# Controller.net
KiCad netlist of a schematic drawn in Altium Designer
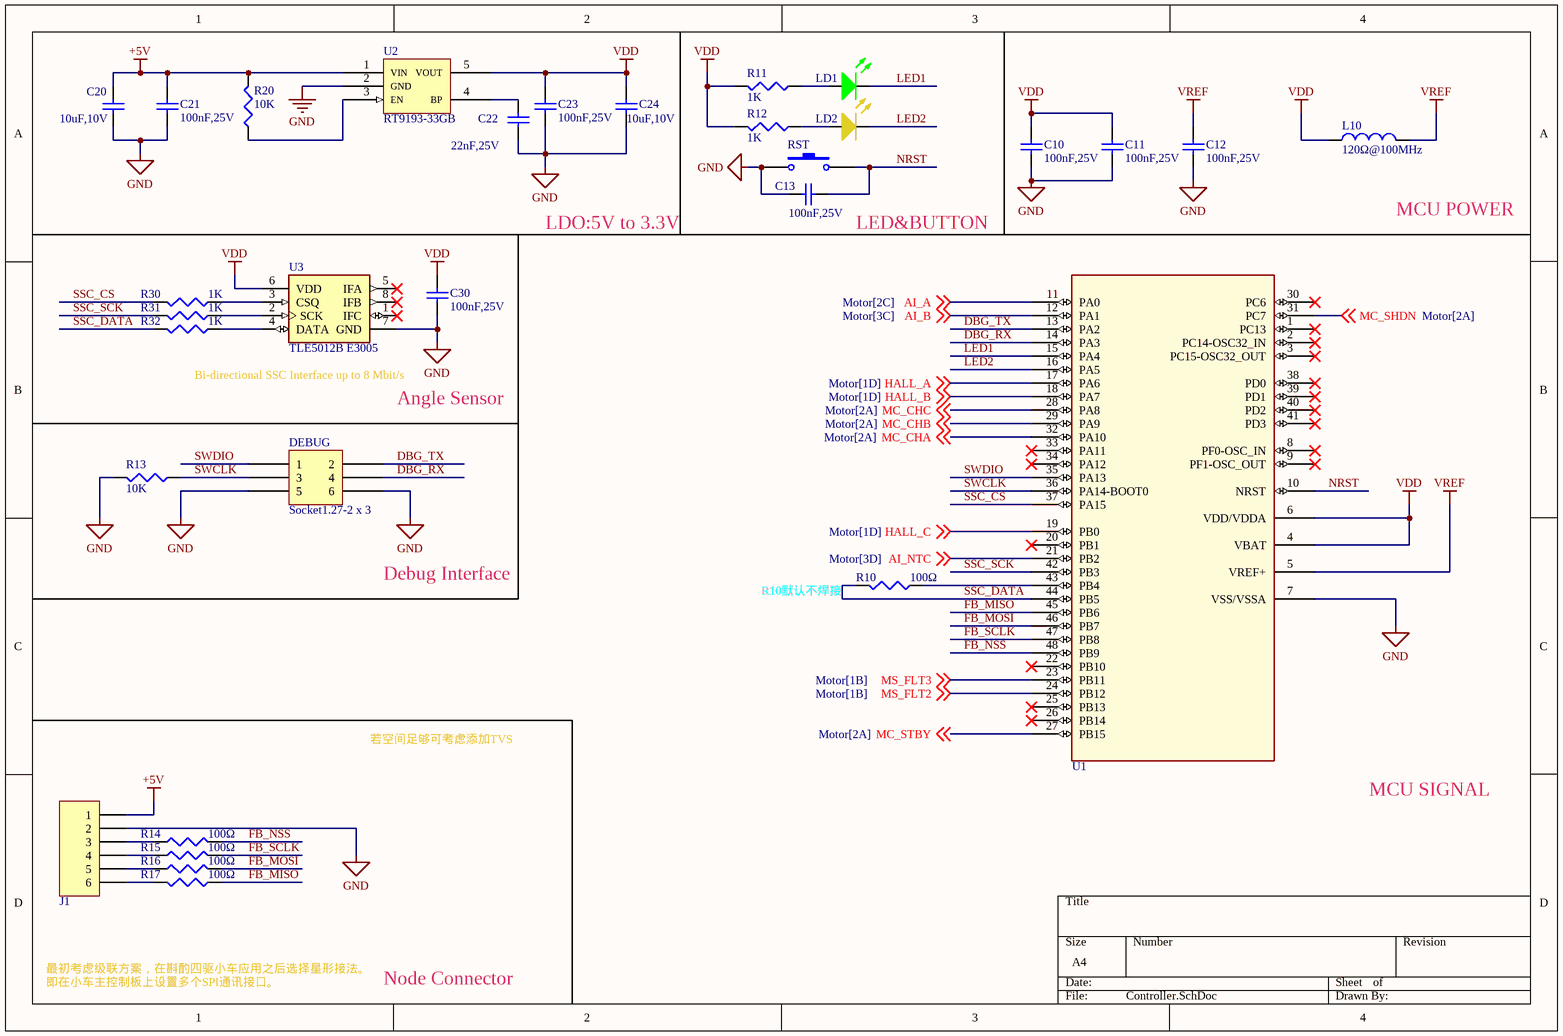
[diagram p0: Controller.SchDoc]

(export (version "E")
  (design (tool "Eeschema 10.0.6"))
  (components
    (comp (ref "C10")
      (value "100nF,25V")
      (footprint "CAPC1005L")
      (description "MLCC, 0402(1005)")
      (fields (field (name "Comment") "MLCC") (field (name "PUBLISHER") "Altium Limited"))
      (libsource (lib "Miscellaneous Devices") (part "Cap"))
    )
    (comp (ref "C11")
      (value "100nF,25V")
      (footprint "CAPC1005L")
      (description "MLCC, 0402(1005)")
      (fields (field (name "Comment") "MLCC") (field (name "PUBLISHER") "Altium Limited"))
      (libsource (lib "Miscellaneous Devices") (part "Cap"))
    )
    (comp (ref "C12")
      (value "100nF,25V")
      (footprint "CAPC1005L")
      (description "MLCC, 0402(1005)")
      (fields (field (name "Comment") "MLCC") (field (name "PUBLISHER") "Altium Limited"))
      (libsource (lib "Miscellaneous Devices") (part "Cap"))
    )
    (comp (ref "C13")
      (value "100nF,25V")
      (footprint "CAPC1005L")
      (description "MLCC, 0402(1005)")
      (fields (field (name "Comment") "MLCC") (field (name "PUBLISHER") "Altium Limited"))
      (libsource (lib "Miscellaneous Devices") (part "Cap"))
    )
    (comp (ref "C20")
      (value "10uF,10V")
      (footprint "CAPC1608L")
      (description "MLCC, 0603(1608)")
      (fields (field (name "Comment") "MLCC") (field (name "PUBLISHER") "Altium Limited"))
      (libsource (lib "Miscellaneous Devices") (part "Cap"))
    )
    (comp (ref "C21")
      (value "100nF,25V")
      (footprint "CAPC1005L")
      (description "MLCC, 0402(1005)")
      (fields (field (name "Comment") "MLCC") (field (name "PUBLISHER") "Altium Limited"))
      (libsource (lib "Miscellaneous Devices") (part "Cap"))
    )
    (comp (ref "C22")
      (value "22nF,25V")
      (footprint "CAPC1005L")
      (description "MLCC, 0402(1005)")
      (fields (field (name "Comment") "MLCC") (field (name "PUBLISHER") "Altium Limited"))
      (libsource (lib "Miscellaneous Devices") (part "Cap"))
    )
    (comp (ref "C23")
      (value "100nF,25V")
      (footprint "CAPC1005L")
      (description "MLCC, 0402(1005)")
      (fields (field (name "Comment") "MLCC") (field (name "PUBLISHER") "Altium Limited"))
      (libsource (lib "Miscellaneous Devices") (part "Cap"))
    )
    (comp (ref "C24")
      (value "10uF,10V")
      (footprint "CAPC1608L")
      (description "MLCC, 0603(1608)")
      (fields (field (name "Comment") "MLCC") (field (name "PUBLISHER") "Altium Limited"))
      (libsource (lib "Miscellaneous Devices") (part "Cap"))
    )
    (comp (ref "C30")
      (value "100nF,25V")
      (footprint "CAPC1005L")
      (description "MLCC, 0402(1005)")
      (fields (field (name "Comment") "MLCC") (field (name "PUBLISHER") "Altium Limited"))
      (libsource (lib "Miscellaneous Devices") (part "Cap"))
    )
    (comp (ref "DEBUG")
      (value "Socket1.27-2 x 3")
      (footprint "Socket_1.27_V_2 x 03")
      (description "Socket with 1.27mm gap, 3x2 pins")
      (libsource (lib "XSS_Connector") (part "Socket1.27-3x2"))
    )
    (comp (ref "J1")
      (value "B6B-PH-K-S")
      (footprint "B6B-PH-K-S")
      (description "B6B-PH-K-S or PH2.0 vertical throughhole,5 pins,Gap:2mm")
      (libsource (lib "XSS_Connector") (part "B6B-PH-K-S"))
    )
    (comp (ref "L10")
      (value "120Ω@100MHz")
      (footprint "0402-A")
      (description "Ferrite Bead")
      (fields (field (name "Comment") "Inductor") (field (name "PUBLISHER") "Altium Limited"))
      (libsource (lib "Miscellaneous Devices") (part "Inductor"))
    )
    (comp (ref "LD1")
      (value "LED_0603_GREEN")
      (footprint "LED_0603_AK_Green")
      (description "GREEN LED, 0603")
      (libsource (lib "XSS_IC") (part "LED_0603_GREEN"))
    )
    (comp (ref "LD2")
      (value "LED")
      (footprint "LED_0603_AK_Yellow")
      (description "YELLOW LED, 0603")
      (libsource (lib "XSS_IC") (part "LED_0603_YELLOW"))
    )
    (comp (ref "R10")
      (value "100Ω")
      (footprint "RESC1005L")
      (description "Resistor, 0402(1005)")
      (fields (field (name "Comment") "RES, SMT") (field (name "PUBLISHER") "Altium Limited"))
      (libsource (lib "Miscellaneous Devices") (part "Res3"))
    )
    (comp (ref "R11")
      (value "1K")
      (footprint "RESC1005L")
      (description "Resistor, 0402(1005)")
      (fields (field (name "Comment") "RES, SMT") (field (name "PUBLISHER") "Altium Limited"))
      (libsource (lib "Miscellaneous Devices") (part "Res3"))
    )
    (comp (ref "R12")
      (value "1K")
      (footprint "RESC1005L")
      (description "Resistor, 0402(1005)")
      (fields (field (name "Comment") "RES, SMT") (field (name "PUBLISHER") "Altium Limited"))
      (libsource (lib "Miscellaneous Devices") (part "Res3"))
    )
    (comp (ref "R13")
      (value "10K")
      (footprint "RESC1005L")
      (description "Resistor, 0402(1005)")
      (fields (field (name "Comment") "RES, SMT") (field (name "PUBLISHER") "Altium Limited"))
      (libsource (lib "Miscellaneous Devices") (part "Res3"))
    )
    (comp (ref "R14")
      (value "100Ω")
      (footprint "RESC1005L")
      (description "Resistor, 0402(1005)")
      (fields (field (name "Comment") "RES, SMT") (field (name "PUBLISHER") "Altium Limited"))
      (libsource (lib "Miscellaneous Devices") (part "Res3"))
    )
    (comp (ref "R15")
      (value "100Ω")
      (footprint "RESC1005L")
      (description "Resistor, 0402(1005)")
      (fields (field (name "Comment") "RES, SMT") (field (name "PUBLISHER") "Altium Limited"))
      (libsource (lib "Miscellaneous Devices") (part "Res3"))
    )
    (comp (ref "R16")
      (value "100Ω")
      (footprint "RESC1005L")
      (description "Resistor, 0402(1005)")
      (fields (field (name "Comment") "RES, SMT") (field (name "PUBLISHER") "Altium Limited"))
      (libsource (lib "Miscellaneous Devices") (part "Res3"))
    )
    (comp (ref "R17")
      (value "100Ω")
      (footprint "RESC1005L")
      (description "Resistor, 0402(1005)")
      (fields (field (name "Comment") "RES, SMT") (field (name "PUBLISHER") "Altium Limited"))
      (libsource (lib "Miscellaneous Devices") (part "Res3"))
    )
    (comp (ref "R20")
      (value "10K")
      (footprint "RESC1005L")
      (description "Resistor, 0402(1005)")
      (fields (field (name "Comment") "RES, SMT") (field (name "PUBLISHER") "Altium Limited"))
      (libsource (lib "Miscellaneous Devices") (part "Res3"))
    )
    (comp (ref "R30")
      (value "1K")
      (footprint "RESC1005L")
      (description "Resistor, 0402(1005)")
      (fields (field (name "Comment") "RES, SMT") (field (name "PUBLISHER") "Altium Limited"))
      (libsource (lib "Miscellaneous Devices") (part "Res3"))
    )
    (comp (ref "R31")
      (value "1K")
      (footprint "RESC1005L")
      (description "Resistor, 0402(1005)")
      (fields (field (name "Comment") "RES, SMT") (field (name "PUBLISHER") "Altium Limited"))
      (libsource (lib "Miscellaneous Devices") (part "Res3"))
    )
    (comp (ref "R32")
      (value "1K")
      (footprint "RESC1005L")
      (description "Resistor, 0402(1005)")
      (fields (field (name "Comment") "RES, SMT") (field (name "PUBLISHER") "Altium Limited"))
      (libsource (lib "Miscellaneous Devices") (part "Res3"))
    )
    (comp (ref "RST")
      (value "switch")
      (footprint "SW2_3*2*0.6")
      (libsource (lib "XSS_IC") (part "SW-SPST-2P"))
    )
    (comp (ref "U1")
      (value "STM32G070CBT6")
      (footprint "LQFP48-L")
      (fields
        (field (name "MANUFACTURER_PART_NUMBER") "stm32g0_lqfp48_t2")
        (field (name "COPYRIGHT") "Copyright (C) 2018 Accelerated Designs. All rights reserved")
      )
      (libsource (lib "ST Microelectronics STM32 G0") (part "STM32G070CBTx"))
    )
    (comp (ref "U2")
      (value "RT9193-33GB")
      (footprint "SOT-25")
      (description "RICHTEK RT9193-xxGB with SOT-23-5. xx could be 15...50(1.5V...5.0V),1H(1.85V),2H(2.85V),4G(4.75V).")
      (libsource (lib "XSS_IC") (part "RT9193-xxGB"))
    )
    (comp (ref "U3")
      (value "TLE5012B E3005")
      (footprint "Infineon_PG-DSO-8")
      (description "Infineon, TLE5012B magnetic angle sensor for steering angle measurement. SOIC-8(PG-DSO-8) package.")
      (libsource (lib "XSS_IC") (part "TLE5012B"))
    )
  )
  (nets
    (net (code "1") (name "+5V") (class "Default")
      (node (ref "C20") (pin "2") (pinfunction "2_2") (pintype "passive"))
      (node (ref "C21") (pin "2") (pinfunction "2_2") (pintype "passive"))
      (node (ref "J1") (pin "1") (pinfunction "1_1") (pintype "passive"))
      (node (ref "R20") (pin "2") (pinfunction "2_2") (pintype "passive"))
      (node (ref "U2") (pin "1") (pinfunction "VIN_1") (pintype "power_in"))
    )
    (net (code "2") (name "/DBG_RX") (class "Default")
      (node (ref "DEBUG") (pin "4") (pinfunction "4_4") (pintype "passive"))
      (node (ref "U1") (pin "14") (pinfunction "PA3_14") (pintype "bidirectional"))
    )
    (net (code "3") (name "/DBG_TX") (class "Default")
      (node (ref "DEBUG") (pin "2") (pinfunction "2_2") (pintype "passive"))
      (node (ref "U1") (pin "13") (pinfunction "PA2_13") (pintype "bidirectional"))
    )
    (net (code "4") (name "/FB_MISO") (class "Default")
      (node (ref "R17") (pin "1") (pinfunction "1_1") (pintype "passive"))
      (node (ref "U1") (pin "45") (pinfunction "PB6_45") (pintype "bidirectional"))
    )
    (net (code "5") (name "/FB_MOSI") (class "Default")
      (node (ref "R16") (pin "2") (pinfunction "2_2") (pintype "passive"))
      (node (ref "U1") (pin "46") (pinfunction "PB7_46") (pintype "bidirectional"))
    )
    (net (code "6") (name "/FB_NSS") (class "Default")
      (node (ref "R14") (pin "2") (pinfunction "2_2") (pintype "passive"))
      (node (ref "U1") (pin "48") (pinfunction "PB9_48") (pintype "bidirectional"))
    )
    (net (code "7") (name "/FB_SCLK") (class "Default")
      (node (ref "R15") (pin "2") (pinfunction "2_2") (pintype "passive"))
      (node (ref "U1") (pin "47") (pinfunction "PB8_47") (pintype "bidirectional"))
    )
    (net (code "8") (name "/LED1") (class "Default")
      (node (ref "LD1") (pin "K") (pinfunction "K_K") (pintype "passive"))
      (node (ref "U1") (pin "15") (pinfunction "PA4_15") (pintype "bidirectional"))
    )
    (net (code "9") (name "/LED2") (class "Default")
      (node (ref "LD2") (pin "K") (pinfunction "K_K") (pintype "passive"))
      (node (ref "U1") (pin "16") (pinfunction "PA5_16") (pintype "bidirectional"))
    )
    (net (code "10") (name "/NRST") (class "Default")
      (node (ref "C13") (pin "1") (pinfunction "1_1") (pintype "passive"))
      (node (ref "RST") (pin "2") (pinfunction "2_2") (pintype "passive"))
      (node (ref "U1") (pin "10") (pinfunction "NRST_10") (pintype "bidirectional"))
    )
    (net (code "11") (name "/SSC_CS") (class "Default")
      (node (ref "R30") (pin "2") (pinfunction "2_2") (pintype "passive"))
      (node (ref "U1") (pin "37") (pinfunction "PA15_37") (pintype "bidirectional"))
    )
    (net (code "12") (name "/SSC_DATA") (class "Default")
      (node (ref "R10") (pin "2") (pinfunction "2_2") (pintype "passive"))
      (node (ref "R32") (pin "2") (pinfunction "2_2") (pintype "passive"))
      (node (ref "U1") (pin "44") (pinfunction "PB5_44") (pintype "bidirectional"))
    )
    (net (code "13") (name "/SSC_SCK") (class "Default")
      (node (ref "R31") (pin "2") (pinfunction "2_2") (pintype "passive"))
      (node (ref "U1") (pin "42") (pinfunction "PB3_42") (pintype "bidirectional"))
    )
    (net (code "14") (name "/SWCLK") (class "Default")
      (node (ref "DEBUG") (pin "3") (pinfunction "3_3") (pintype "passive"))
      (node (ref "R13") (pin "1") (pinfunction "1_1") (pintype "passive"))
      (node (ref "U1") (pin "36") (pinfunction "PA14-BOOT0_36") (pintype "bidirectional"))
    )
    (net (code "15") (name "/SWDIO") (class "Default")
      (node (ref "DEBUG") (pin "1") (pinfunction "1_1") (pintype "passive"))
      (node (ref "U1") (pin "35") (pinfunction "PA13_35") (pintype "bidirectional"))
    )
    (net (code "16") (name "AI_A") (class "Default")
      (node (ref "U1") (pin "11") (pinfunction "PA0_11") (pintype "bidirectional"))
    )
    (net (code "17") (name "AI_B") (class "Default")
      (node (ref "U1") (pin "12") (pinfunction "PA1_12") (pintype "bidirectional"))
    )
    (net (code "18") (name "AI_NTC") (class "Default")
      (node (ref "U1") (pin "21") (pinfunction "PB2_21") (pintype "bidirectional"))
    )
    (net (code "19") (name "GND") (class "Default")
      (node (ref "C10") (pin "1") (pinfunction "1_1") (pintype "passive"))
      (node (ref "C11") (pin "1") (pinfunction "1_1") (pintype "passive"))
      (node (ref "C12") (pin "1") (pinfunction "1_1") (pintype "passive"))
      (node (ref "C13") (pin "2") (pinfunction "2_2") (pintype "passive"))
      (node (ref "C20") (pin "1") (pinfunction "1_1") (pintype "passive"))
      (node (ref "C21") (pin "1") (pinfunction "1_1") (pintype "passive"))
      (node (ref "C22") (pin "1") (pinfunction "1_1") (pintype "passive"))
      (node (ref "C23") (pin "1") (pinfunction "1_1") (pintype "passive"))
      (node (ref "C24") (pin "1") (pinfunction "1_1") (pintype "passive"))
      (node (ref "C30") (pin "1") (pinfunction "1_1") (pintype "passive"))
      (node (ref "DEBUG") (pin "5") (pinfunction "5_5") (pintype "passive"))
      (node (ref "DEBUG") (pin "6") (pinfunction "6_6") (pintype "passive"))
      (node (ref "J1") (pin "2") (pinfunction "2_2") (pintype "passive"))
      (node (ref "R13") (pin "2") (pinfunction "2_2") (pintype "passive"))
      (node (ref "RST") (pin "1") (pinfunction "1_1") (pintype "passive"))
      (node (ref "U1") (pin "7") (pinfunction "VSS/VSSA_7") (pintype "power_in"))
      (node (ref "U2") (pin "2") (pinfunction "GND_2") (pintype "power_in"))
      (node (ref "U3") (pin "7") (pinfunction "GND_7") (pintype "power_in"))
    )
    (net (code "20") (name "HALL_A") (class "Default")
      (node (ref "U1") (pin "17") (pinfunction "PA6_17") (pintype "bidirectional"))
    )
    (net (code "21") (name "HALL_B") (class "Default")
      (node (ref "U1") (pin "18") (pinfunction "PA7_18") (pintype "bidirectional"))
    )
    (net (code "22") (name "HALL_C") (class "Default")
      (node (ref "U1") (pin "19") (pinfunction "PB0_19") (pintype "bidirectional"))
    )
    (net (code "23") (name "MC_CHA") (class "Default")
      (node (ref "U1") (pin "32") (pinfunction "PA10_32") (pintype "bidirectional"))
    )
    (net (code "24") (name "MC_CHB") (class "Default")
      (node (ref "U1") (pin "29") (pinfunction "PA9_29") (pintype "bidirectional"))
    )
    (net (code "25") (name "MC_CHC") (class "Default")
      (node (ref "U1") (pin "28") (pinfunction "PA8_28") (pintype "bidirectional"))
    )
    (net (code "26") (name "MC_SHDN") (class "Default")
      (node (ref "U1") (pin "31") (pinfunction "PC7_31") (pintype "bidirectional"))
    )
    (net (code "27") (name "MC_STBY") (class "Default")
      (node (ref "U1") (pin "27") (pinfunction "PB15_27") (pintype "bidirectional"))
    )
    (net (code "28") (name "MS_FLT2") (class "Default")
      (node (ref "U1") (pin "24") (pinfunction "PB12_24") (pintype "bidirectional"))
    )
    (net (code "29") (name "MS_FLT3") (class "Default")
      (node (ref "U1") (pin "23") (pinfunction "PB11_23") (pintype "bidirectional"))
    )
    (net (code "30") (name "Net-(J1-Pad3)") (class "Default")
      (node (ref "J1") (pin "3") (pinfunction "3_3") (pintype "passive"))
      (node (ref "R14") (pin "1") (pinfunction "1_1") (pintype "passive"))
    )
    (net (code "31") (name "Net-(J1-Pad4)") (class "Default")
      (node (ref "J1") (pin "4") (pinfunction "4_4") (pintype "passive"))
      (node (ref "R15") (pin "1") (pinfunction "1_1") (pintype "passive"))
    )
    (net (code "32") (name "Net-(J1-Pad5)") (class "Default")
      (node (ref "J1") (pin "5") (pinfunction "5_5") (pintype "passive"))
      (node (ref "R16") (pin "1") (pinfunction "1_1") (pintype "passive"))
    )
    (net (code "33") (name "Net-(J1-Pad6)") (class "Default")
      (node (ref "J1") (pin "6") (pinfunction "6_6") (pintype "passive"))
      (node (ref "R17") (pin "2") (pinfunction "2_2") (pintype "passive"))
    )
    (net (code "34") (name "Net-(LD1-PadA)") (class "Default")
      (node (ref "LD1") (pin "A") (pinfunction "A_A") (pintype "passive"))
      (node (ref "R11") (pin "1") (pinfunction "1_1") (pintype "passive"))
    )
    (net (code "35") (name "Net-(LD2-PadA)") (class "Default")
      (node (ref "LD2") (pin "A") (pinfunction "A_A") (pintype "passive"))
      (node (ref "R12") (pin "1") (pinfunction "1_1") (pintype "passive"))
    )
    (net (code "36") (name "Net-(U1-PB4)") (class "Default")
      (node (ref "R10") (pin "1") (pinfunction "1_1") (pintype "passive"))
      (node (ref "U1") (pin "43") (pinfunction "PB4_43") (pintype "bidirectional"))
    )
    (net (code "37") (name "Net-(U2-BP)") (class "Default")
      (node (ref "C22") (pin "2") (pinfunction "2_2") (pintype "passive"))
      (node (ref "U2") (pin "4") (pinfunction "BP_4") (pintype "passive"))
    )
    (net (code "38") (name "Net-(U2-EN)") (class "Default")
      (node (ref "R20") (pin "1") (pinfunction "1_1") (pintype "passive"))
      (node (ref "U2") (pin "3") (pinfunction "EN_3") (pintype "input"))
    )
    (net (code "39") (name "Net-(U3-CSQ)") (class "Default")
      (node (ref "R30") (pin "1") (pinfunction "1_1") (pintype "passive"))
      (node (ref "U3") (pin "3") (pinfunction "CSQ_3") (pintype "input"))
    )
    (net (code "40") (name "Net-(U3-DATA)") (class "Default")
      (node (ref "R32") (pin "1") (pinfunction "1_1") (pintype "passive"))
      (node (ref "U3") (pin "4") (pinfunction "DATA_4") (pintype "bidirectional"))
    )
    (net (code "41") (name "Net-(U3-SCK)") (class "Default")
      (node (ref "R31") (pin "1") (pinfunction "1_1") (pintype "passive"))
      (node (ref "U3") (pin "2") (pinfunction "SCK_2") (pintype "input"))
    )
    (net (code "42") (name "VDD") (class "Default")
      (node (ref "C10") (pin "2") (pinfunction "2_2") (pintype "passive"))
      (node (ref "C11") (pin "2") (pinfunction "2_2") (pintype "passive"))
      (node (ref "C23") (pin "2") (pinfunction "2_2") (pintype "passive"))
      (node (ref "C24") (pin "2") (pinfunction "2_2") (pintype "passive"))
      (node (ref "C30") (pin "2") (pinfunction "2_2") (pintype "passive"))
      (node (ref "L10") (pin "2") (pinfunction "2_2") (pintype "passive"))
      (node (ref "R11") (pin "2") (pinfunction "2_2") (pintype "passive"))
      (node (ref "R12") (pin "2") (pinfunction "2_2") (pintype "passive"))
      (node (ref "U1") (pin "4") (pinfunction "VBAT_4") (pintype "power_in"))
      (node (ref "U1") (pin "6") (pinfunction "VDD/VDDA_6") (pintype "power_in"))
      (node (ref "U2") (pin "5") (pinfunction "VOUT_5") (pintype "power_in"))
      (node (ref "U3") (pin "6") (pinfunction "VDD_6") (pintype "power_in"))
    )
    (net (code "43") (name "VREF") (class "Default")
      (node (ref "C12") (pin "2") (pinfunction "2_2") (pintype "passive"))
      (node (ref "L10") (pin "1") (pinfunction "1_1") (pintype "passive"))
      (node (ref "U1") (pin "5") (pinfunction "VREF+_5") (pintype "power_in"))
    )
    (net (code "44") (name "unconnected-(U1-PA11-Pad33)") (class "Default")
      (node (ref "U1") (pin "33") (pinfunction "PA11_33") (pintype "bidirectional+no_connect"))
    )
    (net (code "45") (name "unconnected-(U1-PA12-Pad34)") (class "Default")
      (node (ref "U1") (pin "34") (pinfunction "PA12_34") (pintype "bidirectional+no_connect"))
    )
    (net (code "46") (name "unconnected-(U1-PB1-Pad20)") (class "Default")
      (node (ref "U1") (pin "20") (pinfunction "PB1_20") (pintype "bidirectional+no_connect"))
    )
    (net (code "47") (name "unconnected-(U1-PB10-Pad22)") (class "Default")
      (node (ref "U1") (pin "22") (pinfunction "PB10_22") (pintype "bidirectional+no_connect"))
    )
    (net (code "48") (name "unconnected-(U1-PB13-Pad25)") (class "Default")
      (node (ref "U1") (pin "25") (pinfunction "PB13_25") (pintype "bidirectional+no_connect"))
    )
    (net (code "49") (name "unconnected-(U1-PB14-Pad26)") (class "Default")
      (node (ref "U1") (pin "26") (pinfunction "PB14_26") (pintype "bidirectional+no_connect"))
    )
    (net (code "50") (name "unconnected-(U1-PC6-Pad30)") (class "Default")
      (node (ref "U1") (pin "30") (pinfunction "PC6_30") (pintype "bidirectional+no_connect"))
    )
    (net (code "51") (name "unconnected-(U1-PC13-Pad1)") (class "Default")
      (node (ref "U1") (pin "1") (pinfunction "PC13_1") (pintype "bidirectional+no_connect"))
    )
    (net (code "52") (name "unconnected-(U1-PC14-OSC32_IN-Pad2)") (class "Default")
      (node (ref "U1") (pin "2") (pinfunction "PC14-OSC32_IN_2") (pintype "bidirectional+no_connect"))
    )
    (net (code "53") (name "unconnected-(U1-PC15-OSC32_OUT-Pad3)") (class "Default")
      (node (ref "U1") (pin "3") (pinfunction "PC15-OSC32_OUT_3") (pintype "bidirectional+no_connect"))
    )
    (net (code "54") (name "unconnected-(U1-PD0-Pad38)") (class "Default")
      (node (ref "U1") (pin "38") (pinfunction "PD0_38") (pintype "bidirectional+no_connect"))
    )
    (net (code "55") (name "unconnected-(U1-PD1-Pad39)") (class "Default")
      (node (ref "U1") (pin "39") (pinfunction "PD1_39") (pintype "bidirectional+no_connect"))
    )
    (net (code "56") (name "unconnected-(U1-PD2-Pad40)") (class "Default")
      (node (ref "U1") (pin "40") (pinfunction "PD2_40") (pintype "bidirectional+no_connect"))
    )
    (net (code "57") (name "unconnected-(U1-PD3-Pad41)") (class "Default")
      (node (ref "U1") (pin "41") (pinfunction "PD3_41") (pintype "bidirectional+no_connect"))
    )
    (net (code "58") (name "unconnected-(U1-PF0-OSC_IN-Pad8)") (class "Default")
      (node (ref "U1") (pin "8") (pinfunction "PF0-OSC_IN_8") (pintype "bidirectional+no_connect"))
    )
    (net (code "59") (name "unconnected-(U1-PF1-OSC_OUT-Pad9)") (class "Default")
      (node (ref "U1") (pin "9") (pinfunction "PF1-OSC_OUT_9") (pintype "bidirectional+no_connect"))
    )
    (net (code "60") (name "unconnected-(U3-IFA-Pad5)") (class "Default")
      (node (ref "U3") (pin "5") (pinfunction "IFA_5") (pintype "output+no_connect"))
    )
    (net (code "61") (name "unconnected-(U3-IFB-Pad8)") (class "Default")
      (node (ref "U3") (pin "8") (pinfunction "IFB_8") (pintype "output+no_connect"))
    )
    (net (code "62") (name "unconnected-(U3-IFC-Pad1)") (class "Default")
      (node (ref "U3") (pin "1") (pinfunction "IFC_1") (pintype "bidirectional+no_connect"))
    )
  )
)
